# main-board.net
KiCad netlist of a schematic drawn in EAGLE
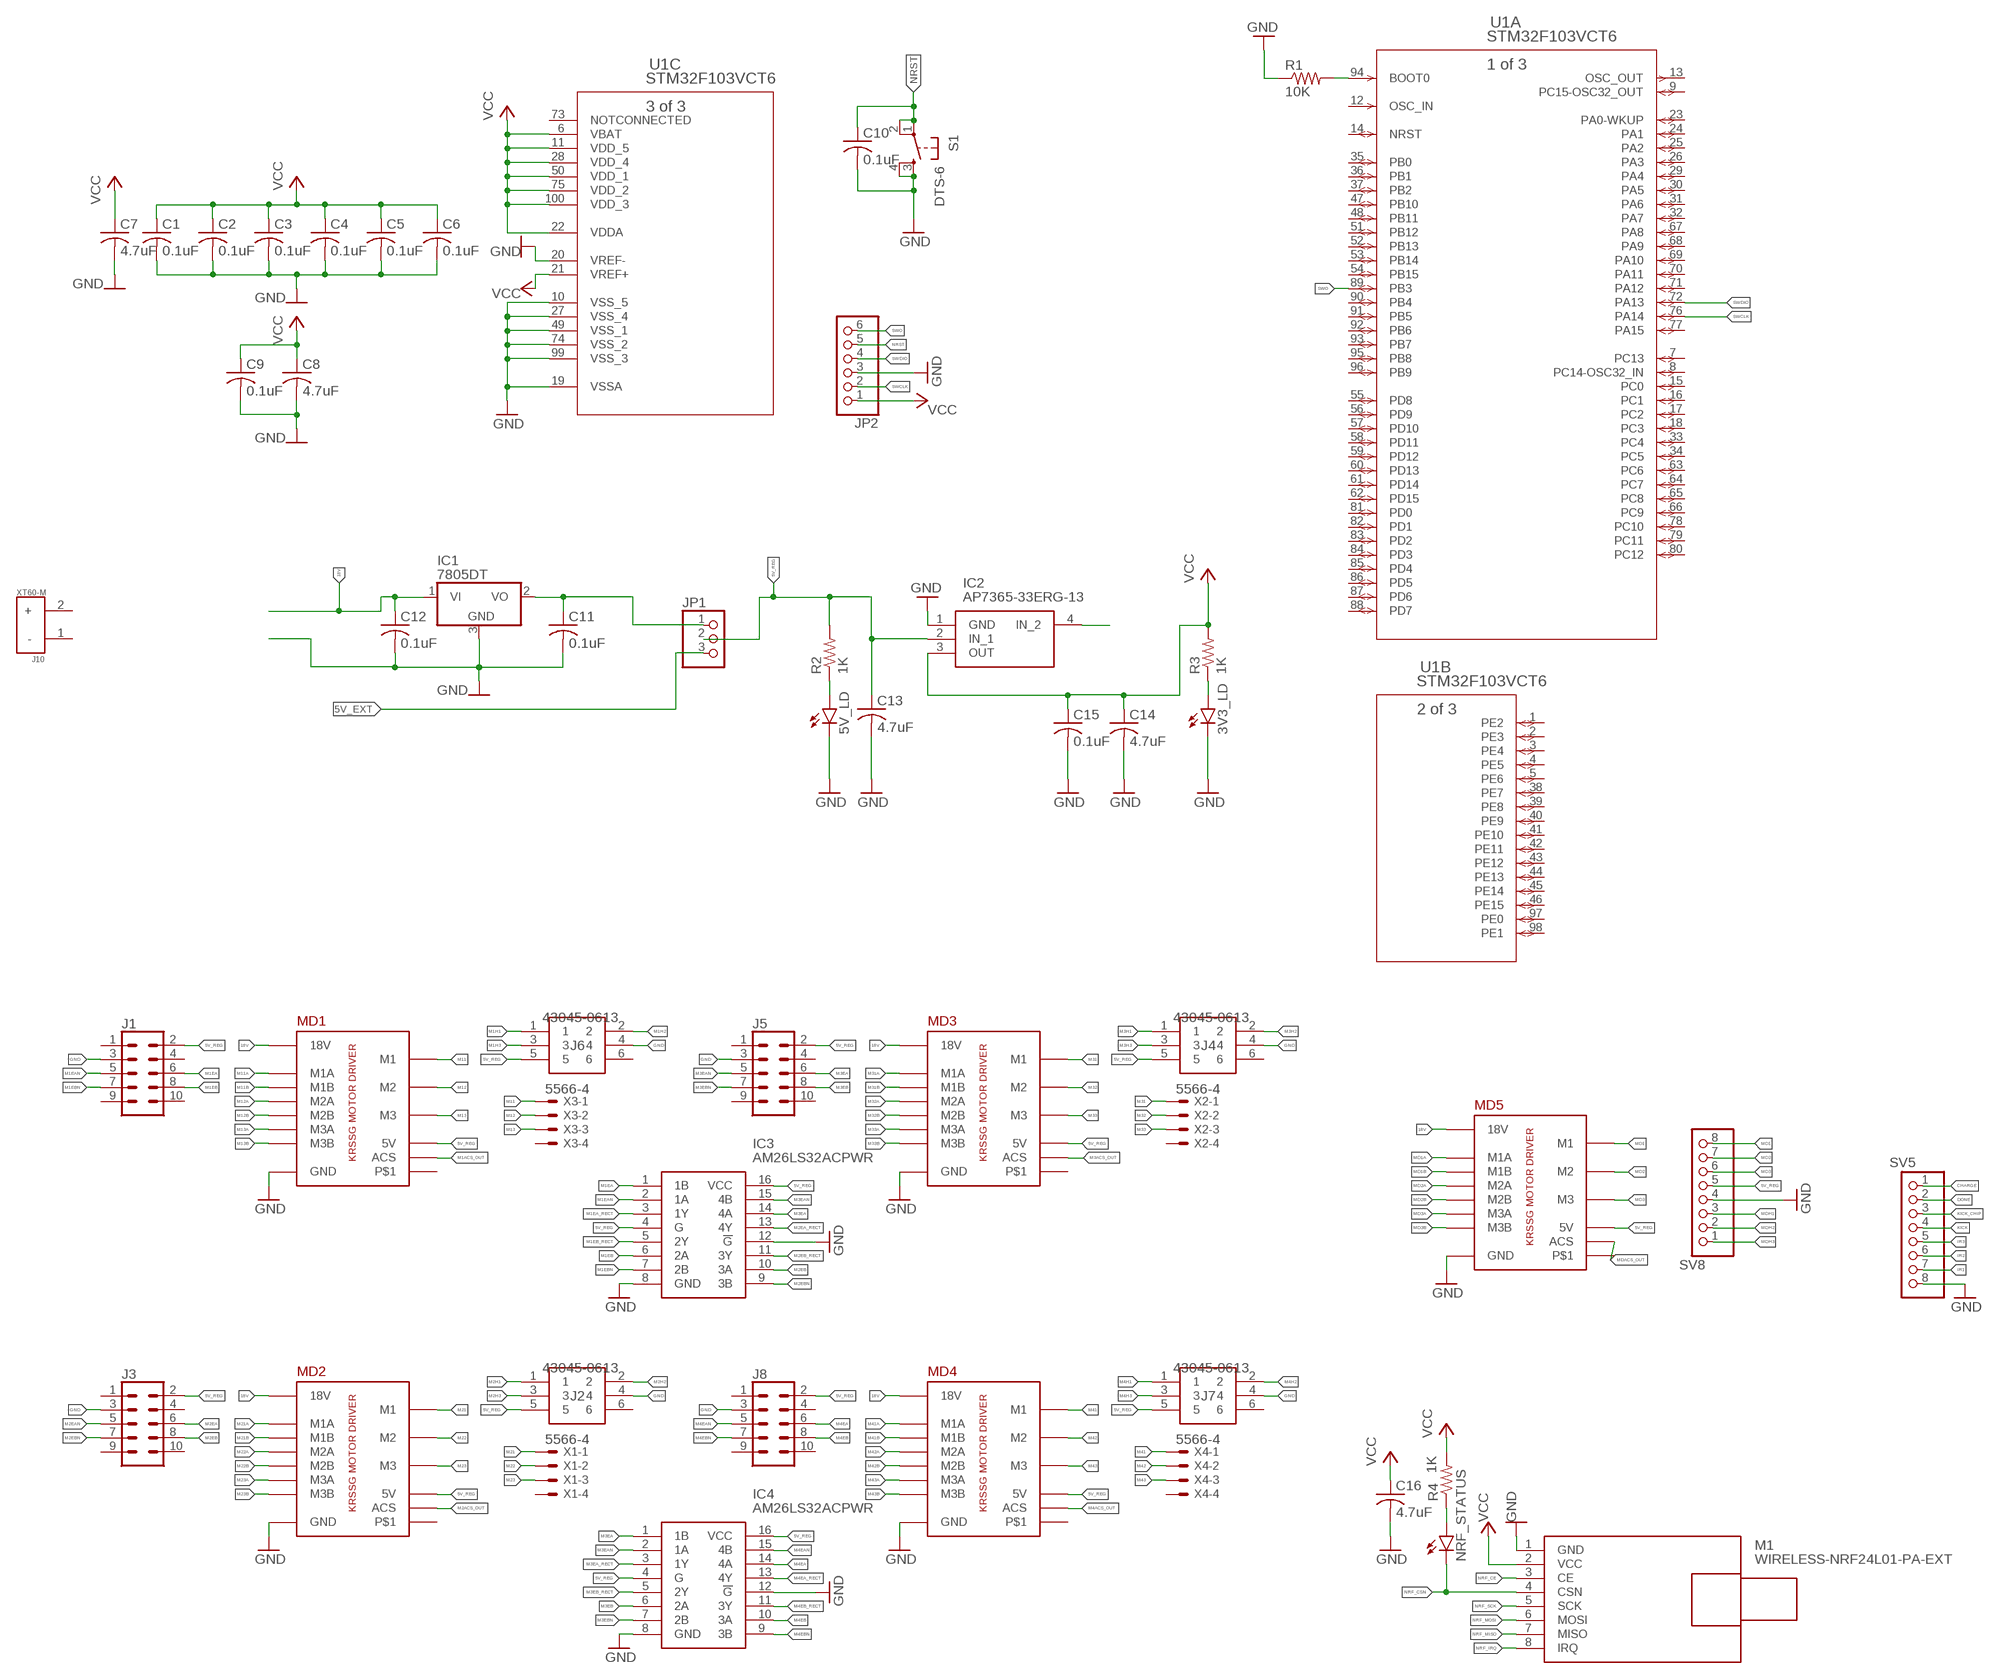
[diagram p0: schematic, sheet 1]

(export (version "E")
  (design (tool "Eeschema 10.0.6"))
  (components
    (comp (ref "3V3_LD")
      (value "LEDCHIPLED_1206")
      (footprint "eagle-import:CHIPLED_1206")
      (libsource (lib "eagle-import") (part "LEDCHIPLED_1206"))
    )
    (comp (ref "5V_LD")
      (value "LEDCHIPLED_1206")
      (footprint "eagle-import:CHIPLED_1206")
      (libsource (lib "eagle-import") (part "LEDCHIPLED_1206"))
    )
    (comp (ref "C1")
      (value "0.1uF")
      (footprint "eagle-import:C1206")
      (libsource (lib "eagle-import") (part "C-USC1206"))
    )
    (comp (ref "C2")
      (value "0.1uF")
      (footprint "eagle-import:C1206")
      (libsource (lib "eagle-import") (part "C-USC1206"))
    )
    (comp (ref "C3")
      (value "0.1uF")
      (footprint "eagle-import:C1206")
      (libsource (lib "eagle-import") (part "C-USC1206"))
    )
    (comp (ref "C4")
      (value "0.1uF")
      (footprint "eagle-import:C1206")
      (libsource (lib "eagle-import") (part "C-USC1206"))
    )
    (comp (ref "C5")
      (value "0.1uF")
      (footprint "eagle-import:C1206")
      (libsource (lib "eagle-import") (part "C-USC1206"))
    )
    (comp (ref "C6")
      (value "0.1uF")
      (footprint "eagle-import:C1206")
      (libsource (lib "eagle-import") (part "C-USC1206"))
    )
    (comp (ref "C7")
      (value "4.7uF")
      (footprint "eagle-import:C1206")
      (libsource (lib "eagle-import") (part "C-USC1206"))
    )
    (comp (ref "C8")
      (value "4.7uF")
      (footprint "eagle-import:C1206")
      (libsource (lib "eagle-import") (part "C-USC1206"))
    )
    (comp (ref "C9")
      (value "0.1uF")
      (footprint "eagle-import:C1206")
      (libsource (lib "eagle-import") (part "C-USC1206"))
    )
    (comp (ref "C10")
      (value "0.1uF")
      (footprint "eagle-import:C1206")
      (libsource (lib "eagle-import") (part "C-USC1206"))
    )
    (comp (ref "C11")
      (value "0.1uF")
      (footprint "eagle-import:C1206")
      (libsource (lib "eagle-import") (part "C-USC1206"))
    )
    (comp (ref "C12")
      (value "0.1uF")
      (footprint "eagle-import:C1206")
      (libsource (lib "eagle-import") (part "C-USC1206"))
    )
    (comp (ref "C13")
      (value "4.7uF")
      (footprint "eagle-import:C1206")
      (libsource (lib "eagle-import") (part "C-USC1206"))
    )
    (comp (ref "C14")
      (value "4.7uF")
      (footprint "eagle-import:C1206")
      (libsource (lib "eagle-import") (part "C-USC1206"))
    )
    (comp (ref "C15")
      (value "0.1uF")
      (footprint "eagle-import:C1206")
      (libsource (lib "eagle-import") (part "C-USC1206"))
    )
    (comp (ref "C16")
      (value "4.7uF")
      (footprint "eagle-import:C1206")
      (libsource (lib "eagle-import") (part "C-USC1206"))
    )
    (comp (ref "IC1")
      (value "7805DT")
      (footprint "eagle-import:TO252")
      (libsource (lib "eagle-import") (part "78DT05"))
    )
    (comp (ref "IC2")
      (value "AP7365-33ERG-13")
      (footprint "eagle-import:SOT230P700X180-4N")
      (libsource (lib "eagle-import") (part "AP7365-33ERG-13"))
    )
    (comp (ref "IC3")
      (value "AM26LS32ACPWR")
      (footprint "eagle-import:SOP65P640X120-16N")
      (fields (field (name "MOUSER_PART_NUMBER") "595-AM26LS32ACPWR"))
      (libsource (lib "eagle-import") (part "AM26LS32ACPWR"))
    )
    (comp (ref "IC4")
      (value "AM26LS32ACPWR")
      (footprint "eagle-import:SOP65P640X120-16N")
      (fields (field (name "MOUSER_PART_NUMBER") "595-AM26LS32ACPWR"))
      (libsource (lib "eagle-import") (part "AM26LS32ACPWR"))
    )
    (comp (ref "J1")
      (value "CONN_05X2SHD_LOCK")
      (footprint "eagle-import:2X5-SHROUDED_LOCK")
      (libsource (lib "eagle-import") (part "CONN_05X2SHD_LOCK"))
    )
    (comp (ref "J2")
      (value "43045-0613")
      (footprint "eagle-import:43045-0613")
      (fields (field (name "MOUSER_PART_NUMBER") "538-43045-0613") (field (name "RS_PART_NUMBER") "6700377P"))
      (libsource (lib "eagle-import") (part "43045-0613"))
    )
    (comp (ref "J3")
      (value "CONN_05X2SHD_LOCK")
      (footprint "eagle-import:2X5-SHROUDED_LOCK")
      (libsource (lib "eagle-import") (part "CONN_05X2SHD_LOCK"))
    )
    (comp (ref "J4")
      (value "43045-0613")
      (footprint "eagle-import:43045-0613")
      (fields (field (name "MOUSER_PART_NUMBER") "538-43045-0613") (field (name "RS_PART_NUMBER") "6700377P"))
      (libsource (lib "eagle-import") (part "43045-0613"))
    )
    (comp (ref "J5")
      (value "CONN_05X2SHD_LOCK")
      (footprint "eagle-import:2X5-SHROUDED_LOCK")
      (libsource (lib "eagle-import") (part "CONN_05X2SHD_LOCK"))
    )
    (comp (ref "J6")
      (value "43045-0613")
      (footprint "eagle-import:43045-0613")
      (fields (field (name "MOUSER_PART_NUMBER") "538-43045-0613") (field (name "RS_PART_NUMBER") "6700377P"))
      (libsource (lib "eagle-import") (part "43045-0613"))
    )
    (comp (ref "J7")
      (value "43045-0613")
      (footprint "eagle-import:43045-0613")
      (fields (field (name "MOUSER_PART_NUMBER") "538-43045-0613") (field (name "RS_PART_NUMBER") "6700377P"))
      (libsource (lib "eagle-import") (part "43045-0613"))
    )
    (comp (ref "J8")
      (value "CONN_05X2SHD_LOCK")
      (footprint "eagle-import:2X5-SHROUDED_LOCK")
      (libsource (lib "eagle-import") (part "CONN_05X2SHD_LOCK"))
    )
    (comp (ref "J10")
      (value "XT60-M")
      (footprint "eagle-import:AMASS_XT60-M")
      (fields (field (name "MF") "AMASS"))
      (libsource (lib "eagle-import") (part "XT60-M"))
    )
    (comp (ref "JP1")
      (value "PINHD-1X3")
      (footprint "eagle-import:1X03")
      (libsource (lib "eagle-import") (part "PINHD-1X3"))
    )
    (comp (ref "JP2")
      (value "PINHD-1X6")
      (footprint "eagle-import:1X06")
      (libsource (lib "eagle-import") (part "PINHD-1X6"))
    )
    (comp (ref "M1")
      (value "WIRELESS-NRF24L01-PA-EXT")
      (footprint "eagle-import:WIRELESS-NRD24L01-PA-EXT")
      (libsource (lib "eagle-import") (part "WIRELESS-NRF24L01-PA-EXT"))
    )
    (comp (ref "MD1")
      (value "KRSSG_MOTOR_DRIVER")
      (footprint "eagle-import:KRSSG_MOTOR_DRIVER")
      (libsource (lib "eagle-import") (part "KRSSG_MOTOR_DRIVER"))
    )
    (comp (ref "MD2")
      (value "KRSSG_MOTOR_DRIVER")
      (footprint "eagle-import:KRSSG_MOTOR_DRIVER")
      (libsource (lib "eagle-import") (part "KRSSG_MOTOR_DRIVER"))
    )
    (comp (ref "MD3")
      (value "KRSSG_MOTOR_DRIVER")
      (footprint "eagle-import:KRSSG_MOTOR_DRIVER")
      (libsource (lib "eagle-import") (part "KRSSG_MOTOR_DRIVER"))
    )
    (comp (ref "MD4")
      (value "KRSSG_MOTOR_DRIVER")
      (footprint "eagle-import:KRSSG_MOTOR_DRIVER")
      (libsource (lib "eagle-import") (part "KRSSG_MOTOR_DRIVER"))
    )
    (comp (ref "MD5")
      (value "KRSSG_MOTOR_DRIVER")
      (footprint "eagle-import:KRSSG_MOTOR_DRIVER")
      (libsource (lib "eagle-import") (part "KRSSG_MOTOR_DRIVER"))
    )
    (comp (ref "NRF_STATUS")
      (value "LEDCHIPLED_1206")
      (footprint "eagle-import:CHIPLED_1206")
      (libsource (lib "eagle-import") (part "LEDCHIPLED_1206"))
    )
    (comp (ref "R1")
      (value "10K")
      (footprint "eagle-import:M1206")
      (libsource (lib "eagle-import") (part "R-US_M1206"))
    )
    (comp (ref "R2")
      (value "1K")
      (footprint "eagle-import:M1206")
      (libsource (lib "eagle-import") (part "R-US_M1206"))
    )
    (comp (ref "R3")
      (value "1K")
      (footprint "eagle-import:M1206")
      (libsource (lib "eagle-import") (part "R-US_M1206"))
    )
    (comp (ref "R4")
      (value "1K")
      (footprint "eagle-import:M1206")
      (libsource (lib "eagle-import") (part "R-US_M1206"))
    )
    (comp (ref "S1")
      (value "DTS-6")
      (footprint "eagle-import:DTS-6")
      (libsource (lib "eagle-import") (part "DTS-6"))
    )
    (comp (ref "SV5")
      (value "PINHD-1X8")
      (footprint "eagle-import:1X08")
      (libsource (lib "eagle-import") (part "PINHD-1X8"))
    )
    (comp (ref "SV8")
      (value "PINHD-1X8")
      (footprint "eagle-import:1X08")
      (libsource (lib "eagle-import") (part "PINHD-1X8"))
    )
    (comp (ref "U1")
      (value "STM32F103VCT6")
      (footprint "eagle-import:LQFP100-14X14MM")
      (fields (field (name "COPYRIGHT") "Copyright (C) 2022 Ultra Librarian. All rights reserved."))
      (libsource (lib "eagle-import") (part "STM32F103VCT6"))
    )
    (comp (ref "X1")
      (value "5566-4")
      (footprint "eagle-import:5566-4")
      (fields (field (name "MF") "MOLEX"))
      (libsource (lib "eagle-import") (part "5566-4"))
    )
    (comp (ref "X2")
      (value "5566-4")
      (footprint "eagle-import:5566-4")
      (fields (field (name "MF") "MOLEX"))
      (libsource (lib "eagle-import") (part "5566-4"))
    )
    (comp (ref "X3")
      (value "5566-4")
      (footprint "eagle-import:5566-4")
      (fields (field (name "MF") "MOLEX"))
      (libsource (lib "eagle-import") (part "5566-4"))
    )
    (comp (ref "X4")
      (value "5566-4")
      (footprint "eagle-import:5566-4")
      (fields (field (name "MF") "MOLEX"))
      (libsource (lib "eagle-import") (part "5566-4"))
    )
  )
  (nets
    (net (code "1") (name "5V_EXT") (class "Default")
      (node (ref "JP1") (pin "3") (pinfunction "3_3") (pintype "passive"))
    )
    (net (code "2") (name "5V_REG") (class "Default")
      (node (ref "C13") (pin "1") (pinfunction "1_1") (pintype "passive"))
      (node (ref "IC2") (pin "2") (pinfunction "IN_1_2") (pintype "input"))
      (node (ref "IC2") (pin "4") (pinfunction "IN_2_4") (pintype "input"))
      (node (ref "IC3") (pin "16") (pinfunction "VCC_16") (pintype "bidirectional"))
      (node (ref "IC3") (pin "4") (pinfunction "G_4") (pintype "bidirectional"))
      (node (ref "IC4") (pin "16") (pinfunction "VCC_16") (pintype "bidirectional"))
      (node (ref "IC4") (pin "4") (pinfunction "G_4") (pintype "bidirectional"))
      (node (ref "J1") (pin "2") (pinfunction "2_2") (pintype "passive"))
      (node (ref "J2") (pin "5") (pinfunction "5_5") (pintype "bidirectional"))
      (node (ref "J3") (pin "2") (pinfunction "2_2") (pintype "passive"))
      (node (ref "J4") (pin "5") (pinfunction "5_5") (pintype "bidirectional"))
      (node (ref "J5") (pin "2") (pinfunction "2_2") (pintype "passive"))
      (node (ref "J6") (pin "5") (pinfunction "5_5") (pintype "bidirectional"))
      (node (ref "J7") (pin "5") (pinfunction "5_5") (pintype "bidirectional"))
      (node (ref "J8") (pin "2") (pinfunction "2_2") (pintype "passive"))
      (node (ref "JP1") (pin "2") (pinfunction "2_2") (pintype "passive"))
      (node (ref "MD1") (pin "5V") (pinfunction "5V_5V") (pintype "bidirectional"))
      (node (ref "MD2") (pin "5V") (pinfunction "5V_5V") (pintype "bidirectional"))
      (node (ref "MD3") (pin "5V") (pinfunction "5V_5V") (pintype "bidirectional"))
      (node (ref "MD4") (pin "5V") (pinfunction "5V_5V") (pintype "bidirectional"))
      (node (ref "MD5") (pin "5V") (pinfunction "5V_5V") (pintype "bidirectional"))
      (node (ref "R2") (pin "2") (pinfunction "2_2") (pintype "passive"))
      (node (ref "SV8") (pin "5") (pinfunction "5_5") (pintype "passive"))
    )
    (net (code "3") (name "18V") (class "Default")
      (node (ref "C12") (pin "1") (pinfunction "1_1") (pintype "passive"))
      (node (ref "IC1") (pin "1") (pinfunction "VI_1") (pintype "input"))
      (node (ref "MD1") (pin "18V") (pinfunction "18V_18V") (pintype "power_in"))
      (node (ref "MD1") (pin "18V_2") (pinfunction "18V_18V_2") (pintype "power_in"))
      (node (ref "MD2") (pin "18V") (pinfunction "18V_18V") (pintype "power_in"))
      (node (ref "MD2") (pin "18V_2") (pinfunction "18V_18V_2") (pintype "power_in"))
      (node (ref "MD3") (pin "18V") (pinfunction "18V_18V") (pintype "power_in"))
      (node (ref "MD3") (pin "18V_2") (pinfunction "18V_18V_2") (pintype "power_in"))
      (node (ref "MD4") (pin "18V") (pinfunction "18V_18V") (pintype "power_in"))
      (node (ref "MD4") (pin "18V_2") (pinfunction "18V_18V_2") (pintype "power_in"))
      (node (ref "MD5") (pin "18V") (pinfunction "18V_18V") (pintype "power_in"))
      (node (ref "MD5") (pin "18V_2") (pinfunction "18V_18V_2") (pintype "power_in"))
    )
    (net (code "4") (name "CHARGE") (class "Default")
      (node (ref "SV5") (pin "1") (pinfunction "1_1") (pintype "passive"))
    )
    (net (code "5") (name "DONE") (class "Default")
      (node (ref "SV5") (pin "2") (pinfunction "2_2") (pintype "passive"))
    )
    (net (code "6") (name "GND") (class "Default")
      (node (ref "3V3_LD") (pin "C") (pinfunction "C_C") (pintype "passive"))
      (node (ref "5V_LD") (pin "C") (pinfunction "C_C") (pintype "passive"))
      (node (ref "C1") (pin "2") (pinfunction "2_2") (pintype "passive"))
      (node (ref "C10") (pin "2") (pinfunction "2_2") (pintype "passive"))
      (node (ref "C11") (pin "2") (pinfunction "2_2") (pintype "passive"))
      (node (ref "C12") (pin "2") (pinfunction "2_2") (pintype "passive"))
      (node (ref "C13") (pin "2") (pinfunction "2_2") (pintype "passive"))
      (node (ref "C14") (pin "2") (pinfunction "2_2") (pintype "passive"))
      (node (ref "C15") (pin "2") (pinfunction "2_2") (pintype "passive"))
      (node (ref "C16") (pin "2") (pinfunction "2_2") (pintype "passive"))
      (node (ref "C2") (pin "2") (pinfunction "2_2") (pintype "passive"))
      (node (ref "C3") (pin "2") (pinfunction "2_2") (pintype "passive"))
      (node (ref "C4") (pin "2") (pinfunction "2_2") (pintype "passive"))
      (node (ref "C5") (pin "2") (pinfunction "2_2") (pintype "passive"))
      (node (ref "C6") (pin "2") (pinfunction "2_2") (pintype "passive"))
      (node (ref "C7") (pin "2") (pinfunction "2_2") (pintype "passive"))
      (node (ref "C8") (pin "2") (pinfunction "2_2") (pintype "passive"))
      (node (ref "C9") (pin "2") (pinfunction "2_2") (pintype "passive"))
      (node (ref "IC1") (pin "3") (pinfunction "GND_3") (pintype "passive"))
      (node (ref "IC2") (pin "1") (pinfunction "GND_1") (pintype "power_in"))
      (node (ref "IC3") (pin "12") (pinfunction "~{G}_12") (pintype "bidirectional"))
      (node (ref "IC3") (pin "8") (pinfunction "GND_8") (pintype "bidirectional"))
      (node (ref "IC4") (pin "12") (pinfunction "~{G}_12") (pintype "bidirectional"))
      (node (ref "IC4") (pin "8") (pinfunction "GND_8") (pintype "bidirectional"))
      (node (ref "J1") (pin "3") (pinfunction "3_3") (pintype "passive"))
      (node (ref "J2") (pin "4") (pinfunction "4_4") (pintype "bidirectional"))
      (node (ref "J3") (pin "3") (pinfunction "3_3") (pintype "passive"))
      (node (ref "J4") (pin "4") (pinfunction "4_4") (pintype "bidirectional"))
      (node (ref "J5") (pin "3") (pinfunction "3_3") (pintype "passive"))
      (node (ref "J6") (pin "4") (pinfunction "4_4") (pintype "bidirectional"))
      (node (ref "J7") (pin "4") (pinfunction "4_4") (pintype "bidirectional"))
      (node (ref "J8") (pin "3") (pinfunction "3_3") (pintype "passive"))
      (node (ref "JP2") (pin "3") (pinfunction "3_3") (pintype "passive"))
      (node (ref "M1") (pin "1") (pinfunction "GND_1") (pintype "power_in"))
      (node (ref "MD1") (pin "GND") (pinfunction "GND_GND") (pintype "power_in"))
      (node (ref "MD1") (pin "GND_2") (pinfunction "GND_GND_2") (pintype "power_in"))
      (node (ref "MD2") (pin "GND") (pinfunction "GND_GND") (pintype "power_in"))
      (node (ref "MD2") (pin "GND_2") (pinfunction "GND_GND_2") (pintype "power_in"))
      (node (ref "MD3") (pin "GND") (pinfunction "GND_GND") (pintype "power_in"))
      (node (ref "MD3") (pin "GND_2") (pinfunction "GND_GND_2") (pintype "power_in"))
      (node (ref "MD4") (pin "GND") (pinfunction "GND_GND") (pintype "power_in"))
      (node (ref "MD4") (pin "GND_2") (pinfunction "GND_GND_2") (pintype "power_in"))
      (node (ref "MD5") (pin "GND") (pinfunction "GND_GND") (pintype "power_in"))
      (node (ref "MD5") (pin "GND_2") (pinfunction "GND_GND_2") (pintype "power_in"))
      (node (ref "R1") (pin "1") (pinfunction "1_1") (pintype "passive"))
      (node (ref "S1") (pin "3") (pinfunction "3_3") (pintype "passive"))
      (node (ref "S1") (pin "4") (pinfunction "4_4") (pintype "passive"))
      (node (ref "SV5") (pin "8") (pinfunction "8_8") (pintype "passive"))
      (node (ref "SV8") (pin "4") (pinfunction "4_4") (pintype "passive"))
      (node (ref "U1") (pin "10") (pinfunction "VSS_5_10") (pintype "power_in"))
      (node (ref "U1") (pin "19") (pinfunction "VSSA_19") (pintype "power_in"))
      (node (ref "U1") (pin "20") (pinfunction "VREF-_20") (pintype "power_in"))
      (node (ref "U1") (pin "27") (pinfunction "VSS_4_27") (pintype "power_in"))
      (node (ref "U1") (pin "49") (pinfunction "VSS_1_49") (pintype "power_in"))
      (node (ref "U1") (pin "74") (pinfunction "VSS_2_74") (pintype "power_in"))
      (node (ref "U1") (pin "99") (pinfunction "VSS_3_99") (pintype "power_in"))
    )
    (net (code "7") (name "IR1") (class "Default")
      (node (ref "SV5") (pin "7") (pinfunction "7_7") (pintype "passive"))
    )
    (net (code "8") (name "IR2") (class "Default")
      (node (ref "SV5") (pin "6") (pinfunction "6_6") (pintype "passive"))
    )
    (net (code "9") (name "IR3") (class "Default")
      (node (ref "SV5") (pin "5") (pinfunction "5_5") (pintype "passive"))
    )
    (net (code "10") (name "KICK") (class "Default")
      (node (ref "SV5") (pin "4") (pinfunction "4_4") (pintype "passive"))
    )
    (net (code "11") (name "KICK_CHIP") (class "Default")
      (node (ref "SV5") (pin "3") (pinfunction "3_3") (pintype "passive"))
    )
    (net (code "12") (name "M1ACS_OUT") (class "Default")
      (node (ref "MD1") (pin "MACS_OUT") (pinfunction "ACS_MACS_OUT") (pintype "bidirectional"))
    )
    (net (code "13") (name "M1EA") (class "Default")
      (node (ref "IC3") (pin "1") (pinfunction "1B_1") (pintype "bidirectional"))
      (node (ref "J1") (pin "6") (pinfunction "6_6") (pintype "passive"))
    )
    (net (code "14") (name "M1EAN") (class "Default")
      (node (ref "IC3") (pin "2") (pinfunction "1A_2") (pintype "bidirectional"))
      (node (ref "J1") (pin "5") (pinfunction "5_5") (pintype "passive"))
    )
    (net (code "15") (name "M1EA_RECT") (class "Default")
      (node (ref "IC3") (pin "3") (pinfunction "1Y_3") (pintype "bidirectional"))
    )
    (net (code "16") (name "M1EB") (class "Default")
      (node (ref "IC3") (pin "6") (pinfunction "2A_6") (pintype "bidirectional"))
      (node (ref "J1") (pin "8") (pinfunction "8_8") (pintype "passive"))
    )
    (net (code "17") (name "M1EBN") (class "Default")
      (node (ref "IC3") (pin "7") (pinfunction "2B_7") (pintype "bidirectional"))
      (node (ref "J1") (pin "7") (pinfunction "7_7") (pintype "passive"))
    )
    (net (code "18") (name "M1EB_RECT") (class "Default")
      (node (ref "IC3") (pin "5") (pinfunction "2Y_5") (pintype "bidirectional"))
    )
    (net (code "19") (name "M1H1") (class "Default")
      (node (ref "J6") (pin "1") (pinfunction "1_1") (pintype "bidirectional"))
    )
    (net (code "20") (name "M1H2") (class "Default")
      (node (ref "J6") (pin "2") (pinfunction "2_2") (pintype "bidirectional"))
    )
    (net (code "21") (name "M1H3") (class "Default")
      (node (ref "J6") (pin "3") (pinfunction "3_3") (pintype "bidirectional"))
    )
    (net (code "22") (name "M2ACS_OUT") (class "Default")
      (node (ref "MD2") (pin "MACS_OUT") (pinfunction "ACS_MACS_OUT") (pintype "bidirectional"))
    )
    (net (code "23") (name "M2EA") (class "Default")
      (node (ref "J3") (pin "6") (pinfunction "6_6") (pintype "passive"))
    )
    (net (code "24") (name "M2EAN") (class "Default")
      (node (ref "J3") (pin "5") (pinfunction "5_5") (pintype "passive"))
    )
    (net (code "25") (name "M2EA_RECT") (class "Default")
      (node (ref "IC3") (pin "13") (pinfunction "4Y_13") (pintype "bidirectional"))
    )
    (net (code "26") (name "M2EB") (class "Default")
      (node (ref "IC3") (pin "10") (pinfunction "3A_10") (pintype "bidirectional"))
      (node (ref "J3") (pin "8") (pinfunction "8_8") (pintype "passive"))
    )
    (net (code "27") (name "M2EBN") (class "Default")
      (node (ref "IC3") (pin "9") (pinfunction "3B_9") (pintype "bidirectional"))
      (node (ref "J3") (pin "7") (pinfunction "7_7") (pintype "passive"))
    )
    (net (code "28") (name "M2EB_RECT") (class "Default")
      (node (ref "IC3") (pin "11") (pinfunction "3Y_11") (pintype "bidirectional"))
    )
    (net (code "29") (name "M2H1") (class "Default")
      (node (ref "J2") (pin "1") (pinfunction "1_1") (pintype "bidirectional"))
    )
    (net (code "30") (name "M2H2") (class "Default")
      (node (ref "J2") (pin "2") (pinfunction "2_2") (pintype "bidirectional"))
    )
    (net (code "31") (name "M2H3") (class "Default")
      (node (ref "J2") (pin "3") (pinfunction "3_3") (pintype "bidirectional"))
    )
    (net (code "32") (name "M3ACS_OUT") (class "Default")
      (node (ref "MD3") (pin "MACS_OUT") (pinfunction "ACS_MACS_OUT") (pintype "bidirectional"))
    )
    (net (code "33") (name "M3EA") (class "Default")
      (node (ref "IC3") (pin "14") (pinfunction "4A_14") (pintype "bidirectional"))
      (node (ref "IC4") (pin "1") (pinfunction "1B_1") (pintype "bidirectional"))
      (node (ref "J5") (pin "6") (pinfunction "6_6") (pintype "passive"))
    )
    (net (code "34") (name "M3EAN") (class "Default")
      (node (ref "IC3") (pin "15") (pinfunction "4B_15") (pintype "bidirectional"))
      (node (ref "IC4") (pin "2") (pinfunction "1A_2") (pintype "bidirectional"))
      (node (ref "J5") (pin "5") (pinfunction "5_5") (pintype "passive"))
    )
    (net (code "35") (name "M3EA_RECT") (class "Default")
      (node (ref "IC4") (pin "3") (pinfunction "1Y_3") (pintype "bidirectional"))
    )
    (net (code "36") (name "M3EB") (class "Default")
      (node (ref "IC4") (pin "6") (pinfunction "2A_6") (pintype "bidirectional"))
      (node (ref "J5") (pin "8") (pinfunction "8_8") (pintype "passive"))
    )
    (net (code "37") (name "M3EBN") (class "Default")
      (node (ref "IC4") (pin "7") (pinfunction "2B_7") (pintype "bidirectional"))
      (node (ref "J5") (pin "7") (pinfunction "7_7") (pintype "passive"))
    )
    (net (code "38") (name "M3EB_RECT") (class "Default")
      (node (ref "IC4") (pin "5") (pinfunction "2Y_5") (pintype "bidirectional"))
    )
    (net (code "39") (name "M3H1") (class "Default")
      (node (ref "J4") (pin "1") (pinfunction "1_1") (pintype "bidirectional"))
    )
    (net (code "40") (name "M3H2") (class "Default")
      (node (ref "J4") (pin "2") (pinfunction "2_2") (pintype "bidirectional"))
    )
    (net (code "41") (name "M3H3") (class "Default")
      (node (ref "J4") (pin "3") (pinfunction "3_3") (pintype "bidirectional"))
    )
    (net (code "42") (name "M4ACS_OUT") (class "Default")
      (node (ref "MD4") (pin "MACS_OUT") (pinfunction "ACS_MACS_OUT") (pintype "bidirectional"))
    )
    (net (code "43") (name "M4EA") (class "Default")
      (node (ref "IC4") (pin "14") (pinfunction "4A_14") (pintype "bidirectional"))
      (node (ref "J8") (pin "6") (pinfunction "6_6") (pintype "passive"))
    )
    (net (code "44") (name "M4EAN") (class "Default")
      (node (ref "IC4") (pin "15") (pinfunction "4B_15") (pintype "bidirectional"))
      (node (ref "J8") (pin "5") (pinfunction "5_5") (pintype "passive"))
    )
    (net (code "45") (name "M4EA_RECT") (class "Default")
      (node (ref "IC4") (pin "13") (pinfunction "4Y_13") (pintype "bidirectional"))
    )
    (net (code "46") (name "M4EB") (class "Default")
      (node (ref "IC4") (pin "10") (pinfunction "3A_10") (pintype "bidirectional"))
      (node (ref "J8") (pin "8") (pinfunction "8_8") (pintype "passive"))
    )
    (net (code "47") (name "M4EBN") (class "Default")
      (node (ref "IC4") (pin "9") (pinfunction "3B_9") (pintype "bidirectional"))
      (node (ref "J8") (pin "7") (pinfunction "7_7") (pintype "passive"))
    )
    (net (code "48") (name "M4EB_RECT") (class "Default")
      (node (ref "IC4") (pin "11") (pinfunction "3Y_11") (pintype "bidirectional"))
    )
    (net (code "49") (name "M4H1") (class "Default")
      (node (ref "J7") (pin "1") (pinfunction "1_1") (pintype "bidirectional"))
    )
    (net (code "50") (name "M4H2") (class "Default")
      (node (ref "J7") (pin "2") (pinfunction "2_2") (pintype "bidirectional"))
    )
    (net (code "51") (name "M4H3") (class "Default")
      (node (ref "J7") (pin "3") (pinfunction "3_3") (pintype "bidirectional"))
    )
    (net (code "52") (name "M11") (class "Default")
      (node (ref "MD1") (pin "M1") (pinfunction "M1_M1") (pintype "output"))
      (node (ref "MD1") (pin "M1_2") (pinfunction "M1_M1_2") (pintype "output"))
      (node (ref "X3") (pin "1") (pinfunction "S_1") (pintype "passive"))
    )
    (net (code "53") (name "M11A") (class "Default")
      (node (ref "MD1") (pin "M1A") (pinfunction "M1A_M1A") (pintype "input"))
    )
    (net (code "54") (name "M11B") (class "Default")
      (node (ref "MD1") (pin "M1B") (pinfunction "M1B_M1B") (pintype "input"))
    )
    (net (code "55") (name "M12") (class "Default")
      (node (ref "MD1") (pin "M2") (pinfunction "M2_M2") (pintype "output"))
      (node (ref "MD1") (pin "M2_2") (pinfunction "M2_M2_2") (pintype "output"))
      (node (ref "X3") (pin "2") (pinfunction "S_2") (pintype "passive"))
    )
    (net (code "56") (name "M12A") (class "Default")
      (node (ref "MD1") (pin "M2A") (pinfunction "M2A_M2A") (pintype "input"))
    )
    (net (code "57") (name "M12B") (class "Default")
      (node (ref "MD1") (pin "M2B") (pinfunction "M2B_M2B") (pintype "input"))
    )
    (net (code "58") (name "M13") (class "Default")
      (node (ref "MD1") (pin "M3") (pinfunction "M3_M3") (pintype "bidirectional"))
      (node (ref "MD1") (pin "M3_2") (pinfunction "M3_M3_2") (pintype "bidirectional"))
      (node (ref "X3") (pin "3") (pinfunction "S_3") (pintype "passive"))
    )
    (net (code "59") (name "M13A") (class "Default")
      (node (ref "MD1") (pin "M3A") (pinfunction "M3A_M3A") (pintype "input"))
    )
    (net (code "60") (name "M13B") (class "Default")
      (node (ref "MD1") (pin "M3B") (pinfunction "M3B_M3B") (pintype "input"))
    )
    (net (code "61") (name "M21") (class "Default")
      (node (ref "MD2") (pin "M1") (pinfunction "M1_M1") (pintype "output"))
      (node (ref "MD2") (pin "M1_2") (pinfunction "M1_M1_2") (pintype "output"))
      (node (ref "X1") (pin "1") (pinfunction "S_1") (pintype "passive"))
    )
    (net (code "62") (name "M21A") (class "Default")
      (node (ref "MD2") (pin "M1A") (pinfunction "M1A_M1A") (pintype "input"))
    )
    (net (code "63") (name "M21B") (class "Default")
      (node (ref "MD2") (pin "M1B") (pinfunction "M1B_M1B") (pintype "input"))
    )
    (net (code "64") (name "M22") (class "Default")
      (node (ref "MD2") (pin "M2") (pinfunction "M2_M2") (pintype "output"))
      (node (ref "MD2") (pin "M2_2") (pinfunction "M2_M2_2") (pintype "output"))
      (node (ref "X1") (pin "2") (pinfunction "S_2") (pintype "passive"))
    )
    (net (code "65") (name "M22A") (class "Default")
      (node (ref "MD2") (pin "M2A") (pinfunction "M2A_M2A") (pintype "input"))
    )
    (net (code "66") (name "M22B") (class "Default")
      (node (ref "MD2") (pin "M2B") (pinfunction "M2B_M2B") (pintype "input"))
    )
    (net (code "67") (name "M23") (class "Default")
      (node (ref "MD2") (pin "M3") (pinfunction "M3_M3") (pintype "bidirectional"))
      (node (ref "MD2") (pin "M3_2") (pinfunction "M3_M3_2") (pintype "bidirectional"))
      (node (ref "X1") (pin "3") (pinfunction "S_3") (pintype "passive"))
    )
    (net (code "68") (name "M23A") (class "Default")
      (node (ref "MD2") (pin "M3A") (pinfunction "M3A_M3A") (pintype "input"))
    )
    (net (code "69") (name "M23B") (class "Default")
      (node (ref "MD2") (pin "M3B") (pinfunction "M3B_M3B") (pintype "input"))
    )
    (net (code "70") (name "M31") (class "Default")
      (node (ref "MD3") (pin "M1") (pinfunction "M1_M1") (pintype "output"))
      (node (ref "MD3") (pin "M1_2") (pinfunction "M1_M1_2") (pintype "output"))
      (node (ref "X2") (pin "1") (pinfunction "S_1") (pintype "passive"))
    )
    (net (code "71") (name "M31A") (class "Default")
      (node (ref "MD3") (pin "M1A") (pinfunction "M1A_M1A") (pintype "input"))
    )
    (net (code "72") (name "M31B") (class "Default")
      (node (ref "MD3") (pin "M1B") (pinfunction "M1B_M1B") (pintype "input"))
    )
    (net (code "73") (name "M32") (class "Default")
      (node (ref "MD3") (pin "M2") (pinfunction "M2_M2") (pintype "output"))
      (node (ref "MD3") (pin "M2_2") (pinfunction "M2_M2_2") (pintype "output"))
      (node (ref "X2") (pin "2") (pinfunction "S_2") (pintype "passive"))
    )
    (net (code "74") (name "M32A") (class "Default")
      (node (ref "MD3") (pin "M2A") (pinfunction "M2A_M2A") (pintype "input"))
    )
    (net (code "75") (name "M32B") (class "Default")
      (node (ref "MD3") (pin "M2B") (pinfunction "M2B_M2B") (pintype "input"))
    )
    (net (code "76") (name "M33") (class "Default")
      (node (ref "MD3") (pin "M3") (pinfunction "M3_M3") (pintype "bidirectional"))
      (node (ref "MD3") (pin "M3_2") (pinfunction "M3_M3_2") (pintype "bidirectional"))
      (node (ref "X2") (pin "3") (pinfunction "S_3") (pintype "passive"))
    )
    (net (code "77") (name "M33A") (class "Default")
      (node (ref "MD3") (pin "M3A") (pinfunction "M3A_M3A") (pintype "input"))
    )
    (net (code "78") (name "M33B") (class "Default")
      (node (ref "MD3") (pin "M3B") (pinfunction "M3B_M3B") (pintype "input"))
    )
    (net (code "79") (name "M41") (class "Default")
      (node (ref "MD4") (pin "M1") (pinfunction "M1_M1") (pintype "output"))
      (node (ref "MD4") (pin "M1_2") (pinfunction "M1_M1_2") (pintype "output"))
      (node (ref "X4") (pin "1") (pinfunction "S_1") (pintype "passive"))
    )
    (net (code "80") (name "M41A") (class "Default")
      (node (ref "MD4") (pin "M1A") (pinfunction "M1A_M1A") (pintype "input"))
    )
    (net (code "81") (name "M41B") (class "Default")
      (node (ref "MD4") (pin "M1B") (pinfunction "M1B_M1B") (pintype "input"))
    )
    (net (code "82") (name "M42") (class "Default")
      (node (ref "MD4") (pin "M2") (pinfunction "M2_M2") (pintype "output"))
      (node (ref "MD4") (pin "M2_2") (pinfunction "M2_M2_2") (pintype "output"))
      (node (ref "X4") (pin "2") (pinfunction "S_2") (pintype "passive"))
    )
    (net (code "83") (name "M42A") (class "Default")
      (node (ref "MD4") (pin "M2A") (pinfunction "M2A_M2A") (pintype "input"))
    )
    (net (code "84") (name "M42B") (class "Default")
      (node (ref "MD4") (pin "M2B") (pinfunction "M2B_M2B") (pintype "input"))
    )
    (net (code "85") (name "M43") (class "Default")
      (node (ref "MD4") (pin "M3") (pinfunction "M3_M3") (pintype "bidirectional"))
      (node (ref "MD4") (pin "M3_2") (pinfunction "M3_M3_2") (pintype "bidirectional"))
      (node (ref "X4") (pin "3") (pinfunction "S_3") (pintype "passive"))
    )
    (net (code "86") (name "M43A") (class "Default")
      (node (ref "MD4") (pin "M3A") (pinfunction "M3A_M3A") (pintype "input"))
    )
    (net (code "87") (name "M43B") (class "Default")
      (node (ref "MD4") (pin "M3B") (pinfunction "M3B_M3B") (pintype "input"))
    )
    (net (code "88") (name "MD1") (class "Default")
      (node (ref "MD5") (pin "M1") (pinfunction "M1_M1") (pintype "output"))
      (node (ref "MD5") (pin "M1_2") (pinfunction "M1_M1_2") (pintype "output"))
      (node (ref "SV8") (pin "8") (pinfunction "8_8") (pintype "passive"))
    )
    (net (code "89") (name "MD1A") (class "Default")
      (node (ref "MD5") (pin "M1A") (pinfunction "M1A_M1A") (pintype "input"))
    )
    (net (code "90") (name "MD1B") (class "Default")
      (node (ref "MD5") (pin "M1B") (pinfunction "M1B_M1B") (pintype "input"))
    )
    (net (code "91") (name "MD2") (class "Default")
      (node (ref "MD5") (pin "M2") (pinfunction "M2_M2") (pintype "output"))
      (node (ref "MD5") (pin "M2_2") (pinfunction "M2_M2_2") (pintype "output"))
      (node (ref "SV8") (pin "7") (pinfunction "7_7") (pintype "passive"))
    )
    (net (code "92") (name "MD2A") (class "Default")
      (node (ref "MD5") (pin "M2A") (pinfunction "M2A_M2A") (pintype "input"))
    )
    (net (code "93") (name "MD2B") (class "Default")
      (node (ref "MD5") (pin "M2B") (pinfunction "M2B_M2B") (pintype "input"))
    )
    (net (code "94") (name "MD3") (class "Default")
      (node (ref "MD5") (pin "M3") (pinfunction "M3_M3") (pintype "bidirectional"))
      (node (ref "MD5") (pin "M3_2") (pinfunction "M3_M3_2") (pintype "bidirectional"))
      (node (ref "SV8") (pin "6") (pinfunction "6_6") (pintype "passive"))
    )
    (net (code "95") (name "MD3A") (class "Default")
      (node (ref "MD5") (pin "M3A") (pinfunction "M3A_M3A") (pintype "input"))
    )
    (net (code "96") (name "MD3B") (class "Default")
      (node (ref "MD5") (pin "M3B") (pinfunction "M3B_M3B") (pintype "input"))
    )
    (net (code "97") (name "MDACS_OUT") (class "Default")
      (node (ref "MD5") (pin "MACS_OUT") (pinfunction "ACS_MACS_OUT") (pintype "bidirectional"))
    )
    (net (code "98") (name "MDH1") (class "Default")
      (node (ref "SV8") (pin "3") (pinfunction "3_3") (pintype "passive"))
    )
    (net (code "99") (name "MDH2") (class "Default")
      (node (ref "SV8") (pin "2") (pinfunction "2_2") (pintype "passive"))
    )
    (net (code "100") (name "MDH3") (class "Default")
      (node (ref "SV8") (pin "1") (pinfunction "1_1") (pintype "passive"))
    )
    (net (code "101") (name "NRF_CE") (class "Default")
      (node (ref "M1") (pin "3") (pinfunction "CE_3") (pintype "bidirectional"))
    )
    (net (code "102") (name "NRF_CSN") (class "Default")
      (node (ref "M1") (pin "4") (pinfunction "CSN_4") (pintype "bidirectional"))
      (node (ref "NRF_STATUS") (pin "C") (pinfunction "C_C") (pintype "passive"))
    )
    (net (code "103") (name "NRF_IRQ") (class "Default")
      (node (ref "M1") (pin "8") (pinfunction "IRQ_8") (pintype "bidirectional"))
    )
    (net (code "104") (name "NRF_MISO") (class "Default")
      (node (ref "M1") (pin "7") (pinfunction "MISO_7") (pintype "bidirectional"))
    )
    (net (code "105") (name "NRF_MOSI") (class "Default")
      (node (ref "M1") (pin "6") (pinfunction "MOSI_6") (pintype "bidirectional"))
    )
    (net (code "106") (name "NRF_SCK") (class "Default")
      (node (ref "M1") (pin "5") (pinfunction "SCK_5") (pintype "bidirectional"))
    )
    (net (code "107") (name "NRST") (class "Default")
      (node (ref "C10") (pin "1") (pinfunction "1_1") (pintype "passive"))
      (node (ref "JP2") (pin "5") (pinfunction "5_5") (pintype "passive"))
      (node (ref "S1") (pin "1") (pinfunction "1_1") (pintype "passive"))
      (node (ref "S1") (pin "2") (pinfunction "2_2") (pintype "passive"))
    )
    (net (code "108") (name "Net-(3V3_LD-PadA)") (class "Default")
      (node (ref "3V3_LD") (pin "A") (pinfunction "A_A") (pintype "passive"))
      (node (ref "R3") (pin "1") (pinfunction "1_1") (pintype "passive"))
    )
    (net (code "109") (name "Net-(5V_LD-PadA)") (class "Default")
      (node (ref "5V_LD") (pin "A") (pinfunction "A_A") (pintype "passive"))
      (node (ref "R2") (pin "1") (pinfunction "1_1") (pintype "passive"))
    )
    (net (code "110") (name "Net-(IC1-VO)") (class "Default")
      (node (ref "C11") (pin "1") (pinfunction "1_1") (pintype "passive"))
      (node (ref "IC1") (pin "2") (pinfunction "VO_2") (pintype "passive"))
      (node (ref "JP1") (pin "1") (pinfunction "1_1") (pintype "passive"))
    )
    (net (code "111") (name "Net-(NRF_STATUS-PadA)") (class "Default")
      (node (ref "NRF_STATUS") (pin "A") (pinfunction "A_A") (pintype "passive"))
      (node (ref "R4") (pin "1") (pinfunction "1_1") (pintype "passive"))
    )
    (net (code "112") (name "Net-(U1A-BOOT0)") (class "Default")
      (node (ref "R1") (pin "2") (pinfunction "2_2") (pintype "passive"))
      (node (ref "U1") (pin "94") (pinfunction "BOOT0_94") (pintype "input"))
    )
    (net (code "113") (name "SWCLK") (class "Default")
      (node (ref "JP2") (pin "2") (pinfunction "2_2") (pintype "passive"))
      (node (ref "U1") (pin "76") (pinfunction "PA14_76") (pintype "bidirectional"))
    )
    (net (code "114") (name "SWDIO") (class "Default")
      (node (ref "JP2") (pin "4") (pinfunction "4_4") (pintype "passive"))
      (node (ref "U1") (pin "72") (pinfunction "PA13_72") (pintype "bidirectional"))
    )
    (net (code "115") (name "SWO") (class "Default")
      (node (ref "JP2") (pin "6") (pinfunction "6_6") (pintype "passive"))
      (node (ref "U1") (pin "89") (pinfunction "PB3_89") (pintype "bidirectional"))
    )
    (net (code "116") (name "VCC") (class "Default")
      (node (ref "C1") (pin "1") (pinfunction "1_1") (pintype "passive"))
      (node (ref "C14") (pin "1") (pinfunction "1_1") (pintype "passive"))
      (node (ref "C15") (pin "1") (pinfunction "1_1") (pintype "passive"))
      (node (ref "C16") (pin "1") (pinfunction "1_1") (pintype "passive"))
      (node (ref "C2") (pin "1") (pinfunction "1_1") (pintype "passive"))
      (node (ref "C3") (pin "1") (pinfunction "1_1") (pintype "passive"))
      (node (ref "C4") (pin "1") (pinfunction "1_1") (pintype "passive"))
      (node (ref "C5") (pin "1") (pinfunction "1_1") (pintype "passive"))
      (node (ref "C6") (pin "1") (pinfunction "1_1") (pintype "passive"))
      (node (ref "C7") (pin "1") (pinfunction "1_1") (pintype "passive"))
      (node (ref "C8") (pin "1") (pinfunction "1_1") (pintype "passive"))
      (node (ref "C9") (pin "1") (pinfunction "1_1") (pintype "passive"))
      (node (ref "IC2") (pin "3") (pinfunction "OUT_3") (pintype "output"))
      (node (ref "JP2") (pin "1") (pinfunction "1_1") (pintype "passive"))
      (node (ref "M1") (pin "2") (pinfunction "VCC_2") (pintype "power_in"))
      (node (ref "R3") (pin "2") (pinfunction "2_2") (pintype "passive"))
      (node (ref "R4") (pin "2") (pinfunction "2_2") (pintype "passive"))
      (node (ref "U1") (pin "100") (pinfunction "VDD_3_100") (pintype "power_in"))
      (node (ref "U1") (pin "11") (pinfunction "VDD_5_11") (pintype "power_in"))
      (node (ref "U1") (pin "21") (pinfunction "VREF+_21") (pintype "power_in"))
      (node (ref "U1") (pin "22") (pinfunction "VDDA_22") (pintype "power_in"))
      (node (ref "U1") (pin "28") (pinfunction "VDD_4_28") (pintype "power_in"))
      (node (ref "U1") (pin "50") (pinfunction "VDD_1_50") (pintype "power_in"))
      (node (ref "U1") (pin "6") (pinfunction "VBAT_6") (pintype "power_in"))
      (node (ref "U1") (pin "75") (pinfunction "VDD_2_75") (pintype "power_in"))
    )
    (net (code "117") (name "unconnected-(J1-Pad1)") (class "Default")
      (node (ref "J1") (pin "1") (pinfunction "1_1") (pintype "passive"))
    )
    (net (code "118") (name "unconnected-(J1-Pad4)") (class "Default")
      (node (ref "J1") (pin "4") (pinfunction "4_4") (pintype "passive"))
    )
    (net (code "119") (name "unconnected-(J1-Pad9)") (class "Default")
      (node (ref "J1") (pin "9") (pinfunction "9_9") (pintype "passive"))
    )
    (net (code "120") (name "unconnected-(J1-Pad10)") (class "Default")
      (node (ref "J1") (pin "10") (pinfunction "10_10") (pintype "passive"))
    )
    (net (code "121") (name "unconnected-(J2-Pad6)") (class "Default")
      (node (ref "J2") (pin "6") (pinfunction "6_6") (pintype "bidirectional"))
    )
    (net (code "122") (name "unconnected-(J3-Pad1)") (class "Default")
      (node (ref "J3") (pin "1") (pinfunction "1_1") (pintype "passive"))
    )
    (net (code "123") (name "unconnected-(J3-Pad4)") (class "Default")
      (node (ref "J3") (pin "4") (pinfunction "4_4") (pintype "passive"))
    )
    (net (code "124") (name "unconnected-(J3-Pad9)") (class "Default")
      (node (ref "J3") (pin "9") (pinfunction "9_9") (pintype "passive"))
    )
    (net (code "125") (name "unconnected-(J3-Pad10)") (class "Default")
      (node (ref "J3") (pin "10") (pinfunction "10_10") (pintype "passive"))
    )
    (net (code "126") (name "unconnected-(J4-Pad6)") (class "Default")
      (node (ref "J4") (pin "6") (pinfunction "6_6") (pintype "bidirectional"))
    )
    (net (code "127") (name "unconnected-(J5-Pad1)") (class "Default")
      (node (ref "J5") (pin "1") (pinfunction "1_1") (pintype "passive"))
    )
    (net (code "128") (name "unconnected-(J5-Pad4)") (class "Default")
      (node (ref "J5") (pin "4") (pinfunction "4_4") (pintype "passive"))
    )
    (net (code "129") (name "unconnected-(J5-Pad9)") (class "Default")
      (node (ref "J5") (pin "9") (pinfunction "9_9") (pintype "passive"))
    )
    (net (code "130") (name "unconnected-(J5-Pad10)") (class "Default")
      (node (ref "J5") (pin "10") (pinfunction "10_10") (pintype "passive"))
    )
    (net (code "131") (name "unconnected-(J6-Pad6)") (class "Default")
      (node (ref "J6") (pin "6") (pinfunction "6_6") (pintype "bidirectional"))
    )
    (net (code "132") (name "unconnected-(J7-Pad6)") (class "Default")
      (node (ref "J7") (pin "6") (pinfunction "6_6") (pintype "bidirectional"))
    )
    (net (code "133") (name "unconnected-(J8-Pad1)") (class "Default")
      (node (ref "J8") (pin "1") (pinfunction "1_1") (pintype "passive"))
    )
    (net (code "134") (name "unconnected-(J8-Pad4)") (class "Default")
      (node (ref "J8") (pin "4") (pinfunction "4_4") (pintype "passive"))
    )
    (net (code "135") (name "unconnected-(J8-Pad9)") (class "Default")
      (node (ref "J8") (pin "9") (pinfunction "9_9") (pintype "passive"))
    )
    (net (code "136") (name "unconnected-(J8-Pad10)") (class "Default")
      (node (ref "J8") (pin "10") (pinfunction "10_10") (pintype "passive"))
    )
    (net (code "137") (name "unconnected-(J10-+-Pad2)") (class "Default")
      (node (ref "J10") (pin "2") (pinfunction "+_2") (pintype "passive"))
    )
    (net (code "138") (name "unconnected-(J10---Pad1)") (class "Default")
      (node (ref "J10") (pin "1") (pinfunction "-_1") (pintype "passive"))
    )
    (net (code "139") (name "unconnected-(MD1-P$1-PadIN17)") (class "Default")
      (node (ref "MD1") (pin "IN17") (pinfunction "P$1_IN17") (pintype "no_connect"))
    )
    (net (code "140") (name "unconnected-(MD1-P$1-PadIN18)") (class "Default")
      (node (ref "MD1") (pin "IN18") (pinfunction "P$1_IN18") (pintype "no_connect"))
    )
    (net (code "141") (name "unconnected-(MD2-P$1-PadIN17)") (class "Default")
      (node (ref "MD2") (pin "IN17") (pinfunction "P$1_IN17") (pintype "no_connect"))
    )
    (net (code "142") (name "unconnected-(MD2-P$1-PadIN18)") (class "Default")
      (node (ref "MD2") (pin "IN18") (pinfunction "P$1_IN18") (pintype "no_connect"))
    )
    (net (code "143") (name "unconnected-(MD3-P$1-PadIN17)") (class "Default")
      (node (ref "MD3") (pin "IN17") (pinfunction "P$1_IN17") (pintype "no_connect"))
    )
    (net (code "144") (name "unconnected-(MD3-P$1-PadIN18)") (class "Default")
      (node (ref "MD3") (pin "IN18") (pinfunction "P$1_IN18") (pintype "no_connect"))
    )
    (net (code "145") (name "unconnected-(MD4-P$1-PadIN17)") (class "Default")
      (node (ref "MD4") (pin "IN17") (pinfunction "P$1_IN17") (pintype "no_connect"))
    )
    (net (code "146") (name "unconnected-(MD4-P$1-PadIN18)") (class "Default")
      (node (ref "MD4") (pin "IN18") (pinfunction "P$1_IN18") (pintype "no_connect"))
    )
    (net (code "147") (name "unconnected-(MD5-P$1-PadIN17)") (class "Default")
      (node (ref "MD5") (pin "IN17") (pinfunction "P$1_IN17") (pintype "no_connect"))
    )
    (net (code "148") (name "unconnected-(MD5-P$1-PadIN18)") (class "Default")
      (node (ref "MD5") (pin "IN18") (pinfunction "P$1_IN18") (pintype "no_connect"))
    )
    (net (code "149") (name "unconnected-(U1A-NRST-Pad14)") (class "Default")
      (node (ref "U1") (pin "14") (pinfunction "NRST_14") (pintype "bidirectional"))
    )
    (net (code "150") (name "unconnected-(U1A-OSC_IN-Pad12)") (class "Default")
      (node (ref "U1") (pin "12") (pinfunction "OSC_IN_12") (pintype "input"))
    )
    (net (code "151") (name "unconnected-(U1A-OSC_OUT-Pad13)") (class "Default")
      (node (ref "U1") (pin "13") (pinfunction "OSC_OUT_13") (pintype "output"))
    )
    (net (code "152") (name "unconnected-(U1A-PA0-WKUP-Pad23)") (class "Default")
      (node (ref "U1") (pin "23") (pinfunction "PA0-WKUP_23") (pintype "bidirectional"))
    )
    (net (code "153") (name "unconnected-(U1A-PA1-Pad24)") (class "Default")
      (node (ref "U1") (pin "24") (pinfunction "PA1_24") (pintype "bidirectional"))
    )
    (net (code "154") (name "unconnected-(U1A-PA2-Pad25)") (class "Default")
      (node (ref "U1") (pin "25") (pinfunction "PA2_25") (pintype "bidirectional"))
    )
    (net (code "155") (name "unconnected-(U1A-PA3-Pad26)") (class "Default")
      (node (ref "U1") (pin "26") (pinfunction "PA3_26") (pintype "bidirectional"))
    )
    (net (code "156") (name "unconnected-(U1A-PA4-Pad29)") (class "Default")
      (node (ref "U1") (pin "29") (pinfunction "PA4_29") (pintype "bidirectional"))
    )
    (net (code "157") (name "unconnected-(U1A-PA5-Pad30)") (class "Default")
      (node (ref "U1") (pin "30") (pinfunction "PA5_30") (pintype "bidirectional"))
    )
    (net (code "158") (name "unconnected-(U1A-PA6-Pad31)") (class "Default")
      (node (ref "U1") (pin "31") (pinfunction "PA6_31") (pintype "bidirectional"))
    )
    (net (code "159") (name "unconnected-(U1A-PA7-Pad32)") (class "Default")
      (node (ref "U1") (pin "32") (pinfunction "PA7_32") (pintype "bidirectional"))
    )
    (net (code "160") (name "unconnected-(U1A-PA8-Pad67)") (class "Default")
      (node (ref "U1") (pin "67") (pinfunction "PA8_67") (pintype "bidirectional"))
    )
    (net (code "161") (name "unconnected-(U1A-PA9-Pad68)") (class "Default")
      (node (ref "U1") (pin "68") (pinfunction "PA9_68") (pintype "bidirectional"))
    )
    (net (code "162") (name "unconnected-(U1A-PA10-Pad69)") (class "Default")
      (node (ref "U1") (pin "69") (pinfunction "PA10_69") (pintype "bidirectional"))
    )
    (net (code "163") (name "unconnected-(U1A-PA11-Pad70)") (class "Default")
      (node (ref "U1") (pin "70") (pinfunction "PA11_70") (pintype "bidirectional"))
    )
    (net (code "164") (name "unconnected-(U1A-PA12-Pad71)") (class "Default")
      (node (ref "U1") (pin "71") (pinfunction "PA12_71") (pintype "bidirectional"))
    )
    (net (code "165") (name "unconnected-(U1A-PA15-Pad77)") (class "Default")
      (node (ref "U1") (pin "77") (pinfunction "PA15_77") (pintype "bidirectional"))
    )
    (net (code "166") (name "unconnected-(U1A-PB0-Pad35)") (class "Default")
      (node (ref "U1") (pin "35") (pinfunction "PB0_35") (pintype "bidirectional"))
    )
    (net (code "167") (name "unconnected-(U1A-PB1-Pad36)") (class "Default")
      (node (ref "U1") (pin "36") (pinfunction "PB1_36") (pintype "bidirectional"))
    )
    (net (code "168") (name "unconnected-(U1A-PB2-Pad37)") (class "Default")
      (node (ref "U1") (pin "37") (pinfunction "PB2_37") (pintype "bidirectional"))
    )
    (net (code "169") (name "unconnected-(U1A-PB4-Pad90)") (class "Default")
      (node (ref "U1") (pin "90") (pinfunction "PB4_90") (pintype "bidirectional"))
    )
    (net (code "170") (name "unconnected-(U1A-PB5-Pad91)") (class "Default")
      (node (ref "U1") (pin "91") (pinfunction "PB5_91") (pintype "bidirectional"))
    )
    (net (code "171") (name "unconnected-(U1A-PB6-Pad92)") (class "Default")
      (node (ref "U1") (pin "92") (pinfunction "PB6_92") (pintype "bidirectional"))
    )
    (net (code "172") (name "unconnected-(U1A-PB7-Pad93)") (class "Default")
      (node (ref "U1") (pin "93") (pinfunction "PB7_93") (pintype "bidirectional"))
    )
    (net (code "173") (name "unconnected-(U1A-PB8-Pad95)") (class "Default")
      (node (ref "U1") (pin "95") (pinfunction "PB8_95") (pintype "bidirectional"))
    )
    (net (code "174") (name "unconnected-(U1A-PB9-Pad96)") (class "Default")
      (node (ref "U1") (pin "96") (pinfunction "PB9_96") (pintype "bidirectional"))
    )
    (net (code "175") (name "unconnected-(U1A-PB10-Pad47)") (class "Default")
      (node (ref "U1") (pin "47") (pinfunction "PB10_47") (pintype "bidirectional"))
    )
    (net (code "176") (name "unconnected-(U1A-PB11-Pad48)") (class "Default")
      (node (ref "U1") (pin "48") (pinfunction "PB11_48") (pintype "bidirectional"))
    )
    (net (code "177") (name "unconnected-(U1A-PB12-Pad51)") (class "Default")
      (node (ref "U1") (pin "51") (pinfunction "PB12_51") (pintype "bidirectional"))
    )
    (net (code "178") (name "unconnected-(U1A-PB13-Pad52)") (class "Default")
      (node (ref "U1") (pin "52") (pinfunction "PB13_52") (pintype "bidirectional"))
    )
    (net (code "179") (name "unconnected-(U1A-PB14-Pad53)") (class "Default")
      (node (ref "U1") (pin "53") (pinfunction "PB14_53") (pintype "bidirectional"))
    )
    (net (code "180") (name "unconnected-(U1A-PB15-Pad54)") (class "Default")
      (node (ref "U1") (pin "54") (pinfunction "PB15_54") (pintype "bidirectional"))
    )
    (net (code "181") (name "unconnected-(U1A-PC0-Pad15)") (class "Default")
      (node (ref "U1") (pin "15") (pinfunction "PC0_15") (pintype "bidirectional"))
    )
    (net (code "182") (name "unconnected-(U1A-PC1-Pad16)") (class "Default")
      (node (ref "U1") (pin "16") (pinfunction "PC1_16") (pintype "bidirectional"))
    )
    (net (code "183") (name "unconnected-(U1A-PC2-Pad17)") (class "Default")
      (node (ref "U1") (pin "17") (pinfunction "PC2_17") (pintype "bidirectional"))
    )
    (net (code "184") (name "unconnected-(U1A-PC3-Pad18)") (class "Default")
      (node (ref "U1") (pin "18") (pinfunction "PC3_18") (pintype "bidirectional"))
    )
    (net (code "185") (name "unconnected-(U1A-PC4-Pad33)") (class "Default")
      (node (ref "U1") (pin "33") (pinfunction "PC4_33") (pintype "bidirectional"))
    )
    (net (code "186") (name "unconnected-(U1A-PC5-Pad34)") (class "Default")
      (node (ref "U1") (pin "34") (pinfunction "PC5_34") (pintype "bidirectional"))
    )
    (net (code "187") (name "unconnected-(U1A-PC6-Pad63)") (class "Default")
      (node (ref "U1") (pin "63") (pinfunction "PC6_63") (pintype "bidirectional"))
    )
    (net (code "188") (name "unconnected-(U1A-PC7-Pad64)") (class "Default")
      (node (ref "U1") (pin "64") (pinfunction "PC7_64") (pintype "bidirectional"))
    )
    (net (code "189") (name "unconnected-(U1A-PC8-Pad65)") (class "Default")
      (node (ref "U1") (pin "65") (pinfunction "PC8_65") (pintype "bidirectional"))
    )
    (net (code "190") (name "unconnected-(U1A-PC9-Pad66)") (class "Default")
      (node (ref "U1") (pin "66") (pinfunction "PC9_66") (pintype "bidirectional"))
    )
    (net (code "191") (name "unconnected-(U1A-PC10-Pad78)") (class "Default")
      (node (ref "U1") (pin "78") (pinfunction "PC10_78") (pintype "bidirectional"))
    )
    (net (code "192") (name "unconnected-(U1A-PC11-Pad79)") (class "Default")
      (node (ref "U1") (pin "79") (pinfunction "PC11_79") (pintype "bidirectional"))
    )
    (net (code "193") (name "unconnected-(U1A-PC12-Pad80)") (class "Default")
      (node (ref "U1") (pin "80") (pinfunction "PC12_80") (pintype "bidirectional"))
    )
    (net (code "194") (name "unconnected-(U1A-PC13-Pad7)") (class "Default")
      (node (ref "U1") (pin "7") (pinfunction "PC13_7") (pintype "bidirectional"))
    )
    (net (code "195") (name "unconnected-(U1A-PC14-OSC32_IN-Pad8)") (class "Default")
      (node (ref "U1") (pin "8") (pinfunction "PC14-OSC32_IN_8") (pintype "bidirectional"))
    )
    (net (code "196") (name "unconnected-(U1A-PC15-OSC32_OUT-Pad9)") (class "Default")
      (node (ref "U1") (pin "9") (pinfunction "PC15-OSC32_OUT_9") (pintype "bidirectional"))
    )
    (net (code "197") (name "unconnected-(U1A-PD0-Pad81)") (class "Default")
      (node (ref "U1") (pin "81") (pinfunction "PD0_81") (pintype "bidirectional"))
    )
    (net (code "198") (name "unconnected-(U1A-PD1-Pad82)") (class "Default")
      (node (ref "U1") (pin "82") (pinfunction "PD1_82") (pintype "bidirectional"))
    )
    (net (code "199") (name "unconnected-(U1A-PD2-Pad83)") (class "Default")
      (node (ref "U1") (pin "83") (pinfunction "PD2_83") (pintype "bidirectional"))
    )
    (net (code "200") (name "unconnected-(U1A-PD3-Pad84)") (class "Default")
      (node (ref "U1") (pin "84") (pinfunction "PD3_84") (pintype "bidirectional"))
    )
    (net (code "201") (name "unconnected-(U1A-PD4-Pad85)") (class "Default")
      (node (ref "U1") (pin "85") (pinfunction "PD4_85") (pintype "bidirectional"))
    )
    (net (code "202") (name "unconnected-(U1A-PD5-Pad86)") (class "Default")
      (node (ref "U1") (pin "86") (pinfunction "PD5_86") (pintype "bidirectional"))
    )
    (net (code "203") (name "unconnected-(U1A-PD6-Pad87)") (class "Default")
      (node (ref "U1") (pin "87") (pinfunction "PD6_87") (pintype "bidirectional"))
    )
    (net (code "204") (name "unconnected-(U1A-PD7-Pad88)") (class "Default")
      (node (ref "U1") (pin "88") (pinfunction "PD7_88") (pintype "bidirectional"))
    )
    (net (code "205") (name "unconnected-(U1A-PD8-Pad55)") (class "Default")
      (node (ref "U1") (pin "55") (pinfunction "PD8_55") (pintype "bidirectional"))
    )
    (net (code "206") (name "unconnected-(U1A-PD9-Pad56)") (class "Default")
      (node (ref "U1") (pin "56") (pinfunction "PD9_56") (pintype "bidirectional"))
    )
    (net (code "207") (name "unconnected-(U1A-PD10-Pad57)") (class "Default")
      (node (ref "U1") (pin "57") (pinfunction "PD10_57") (pintype "bidirectional"))
    )
    (net (code "208") (name "unconnected-(U1A-PD11-Pad58)") (class "Default")
      (node (ref "U1") (pin "58") (pinfunction "PD11_58") (pintype "bidirectional"))
    )
    (net (code "209") (name "unconnected-(U1A-PD12-Pad59)") (class "Default")
      (node (ref "U1") (pin "59") (pinfunction "PD12_59") (pintype "bidirectional"))
    )
    (net (code "210") (name "unconnected-(U1A-PD13-Pad60)") (class "Default")
      (node (ref "U1") (pin "60") (pinfunction "PD13_60") (pintype "bidirectional"))
    )
    (net (code "211") (name "unconnected-(U1A-PD14-Pad61)") (class "Default")
      (node (ref "U1") (pin "61") (pinfunction "PD14_61") (pintype "bidirectional"))
    )
    (net (code "212") (name "unconnected-(U1A-PD15-Pad62)") (class "Default")
      (node (ref "U1") (pin "62") (pinfunction "PD15_62") (pintype "bidirectional"))
    )
    (net (code "213") (name "unconnected-(U1B-PE0-Pad97)") (class "Default")
      (node (ref "U1") (pin "97") (pinfunction "PE0_97") (pintype "bidirectional"))
    )
    (net (code "214") (name "unconnected-(U1B-PE1-Pad98)") (class "Default")
      (node (ref "U1") (pin "98") (pinfunction "PE1_98") (pintype "bidirectional"))
    )
    (net (code "215") (name "unconnected-(U1B-PE2-Pad1)") (class "Default")
      (node (ref "U1") (pin "1") (pinfunction "PE2_1") (pintype "bidirectional"))
    )
    (net (code "216") (name "unconnected-(U1B-PE3-Pad2)") (class "Default")
      (node (ref "U1") (pin "2") (pinfunction "PE3_2") (pintype "bidirectional"))
    )
    (net (code "217") (name "unconnected-(U1B-PE4-Pad3)") (class "Default")
      (node (ref "U1") (pin "3") (pinfunction "PE4_3") (pintype "bidirectional"))
    )
    (net (code "218") (name "unconnected-(U1B-PE5-Pad4)") (class "Default")
      (node (ref "U1") (pin "4") (pinfunction "PE5_4") (pintype "bidirectional"))
    )
    (net (code "219") (name "unconnected-(U1B-PE6-Pad5)") (class "Default")
      (node (ref "U1") (pin "5") (pinfunction "PE6_5") (pintype "bidirectional"))
    )
    (net (code "220") (name "unconnected-(U1B-PE7-Pad38)") (class "Default")
      (node (ref "U1") (pin "38") (pinfunction "PE7_38") (pintype "bidirectional"))
    )
    (net (code "221") (name "unconnected-(U1B-PE8-Pad39)") (class "Default")
      (node (ref "U1") (pin "39") (pinfunction "PE8_39") (pintype "bidirectional"))
    )
    (net (code "222") (name "unconnected-(U1B-PE9-Pad40)") (class "Default")
      (node (ref "U1") (pin "40") (pinfunction "PE9_40") (pintype "bidirectional"))
    )
    (net (code "223") (name "unconnected-(U1B-PE10-Pad41)") (class "Default")
      (node (ref "U1") (pin "41") (pinfunction "PE10_41") (pintype "bidirectional"))
    )
    (net (code "224") (name "unconnected-(U1B-PE11-Pad42)") (class "Default")
      (node (ref "U1") (pin "42") (pinfunction "PE11_42") (pintype "bidirectional"))
    )
    (net (code "225") (name "unconnected-(U1B-PE12-Pad43)") (class "Default")
      (node (ref "U1") (pin "43") (pinfunction "PE12_43") (pintype "bidirectional"))
    )
    (net (code "226") (name "unconnected-(U1B-PE13-Pad44)") (class "Default")
      (node (ref "U1") (pin "44") (pinfunction "PE13_44") (pintype "bidirectional"))
    )
    (net (code "227") (name "unconnected-(U1B-PE14-Pad45)") (class "Default")
      (node (ref "U1") (pin "45") (pinfunction "PE14_45") (pintype "bidirectional"))
    )
    (net (code "228") (name "unconnected-(U1B-PE15-Pad46)") (class "Default")
      (node (ref "U1") (pin "46") (pinfunction "PE15_46") (pintype "bidirectional"))
    )
    (net (code "229") (name "unconnected-(U1C-NOTCONNECTED-Pad73)") (class "Default")
      (node (ref "U1") (pin "73") (pinfunction "NOTCONNECTED_73") (pintype "no_connect"))
    )
    (net (code "230") (name "unconnected-(X1D-S-Pad4)") (class "Default")
      (node (ref "X1") (pin "4") (pinfunction "S_4") (pintype "passive"))
    )
    (net (code "231") (name "unconnected-(X2D-S-Pad4)") (class "Default")
      (node (ref "X2") (pin "4") (pinfunction "S_4") (pintype "passive"))
    )
    (net (code "232") (name "unconnected-(X3D-S-Pad4)") (class "Default")
      (node (ref "X3") (pin "4") (pinfunction "S_4") (pintype "passive"))
    )
    (net (code "233") (name "unconnected-(X4D-S-Pad4)") (class "Default")
      (node (ref "X4") (pin "4") (pinfunction "S_4") (pintype "passive"))
    )
  )
)
